# ESP8266_Blind_Board_V2.net
KiCad netlist of a schematic drawn in EasyEDA
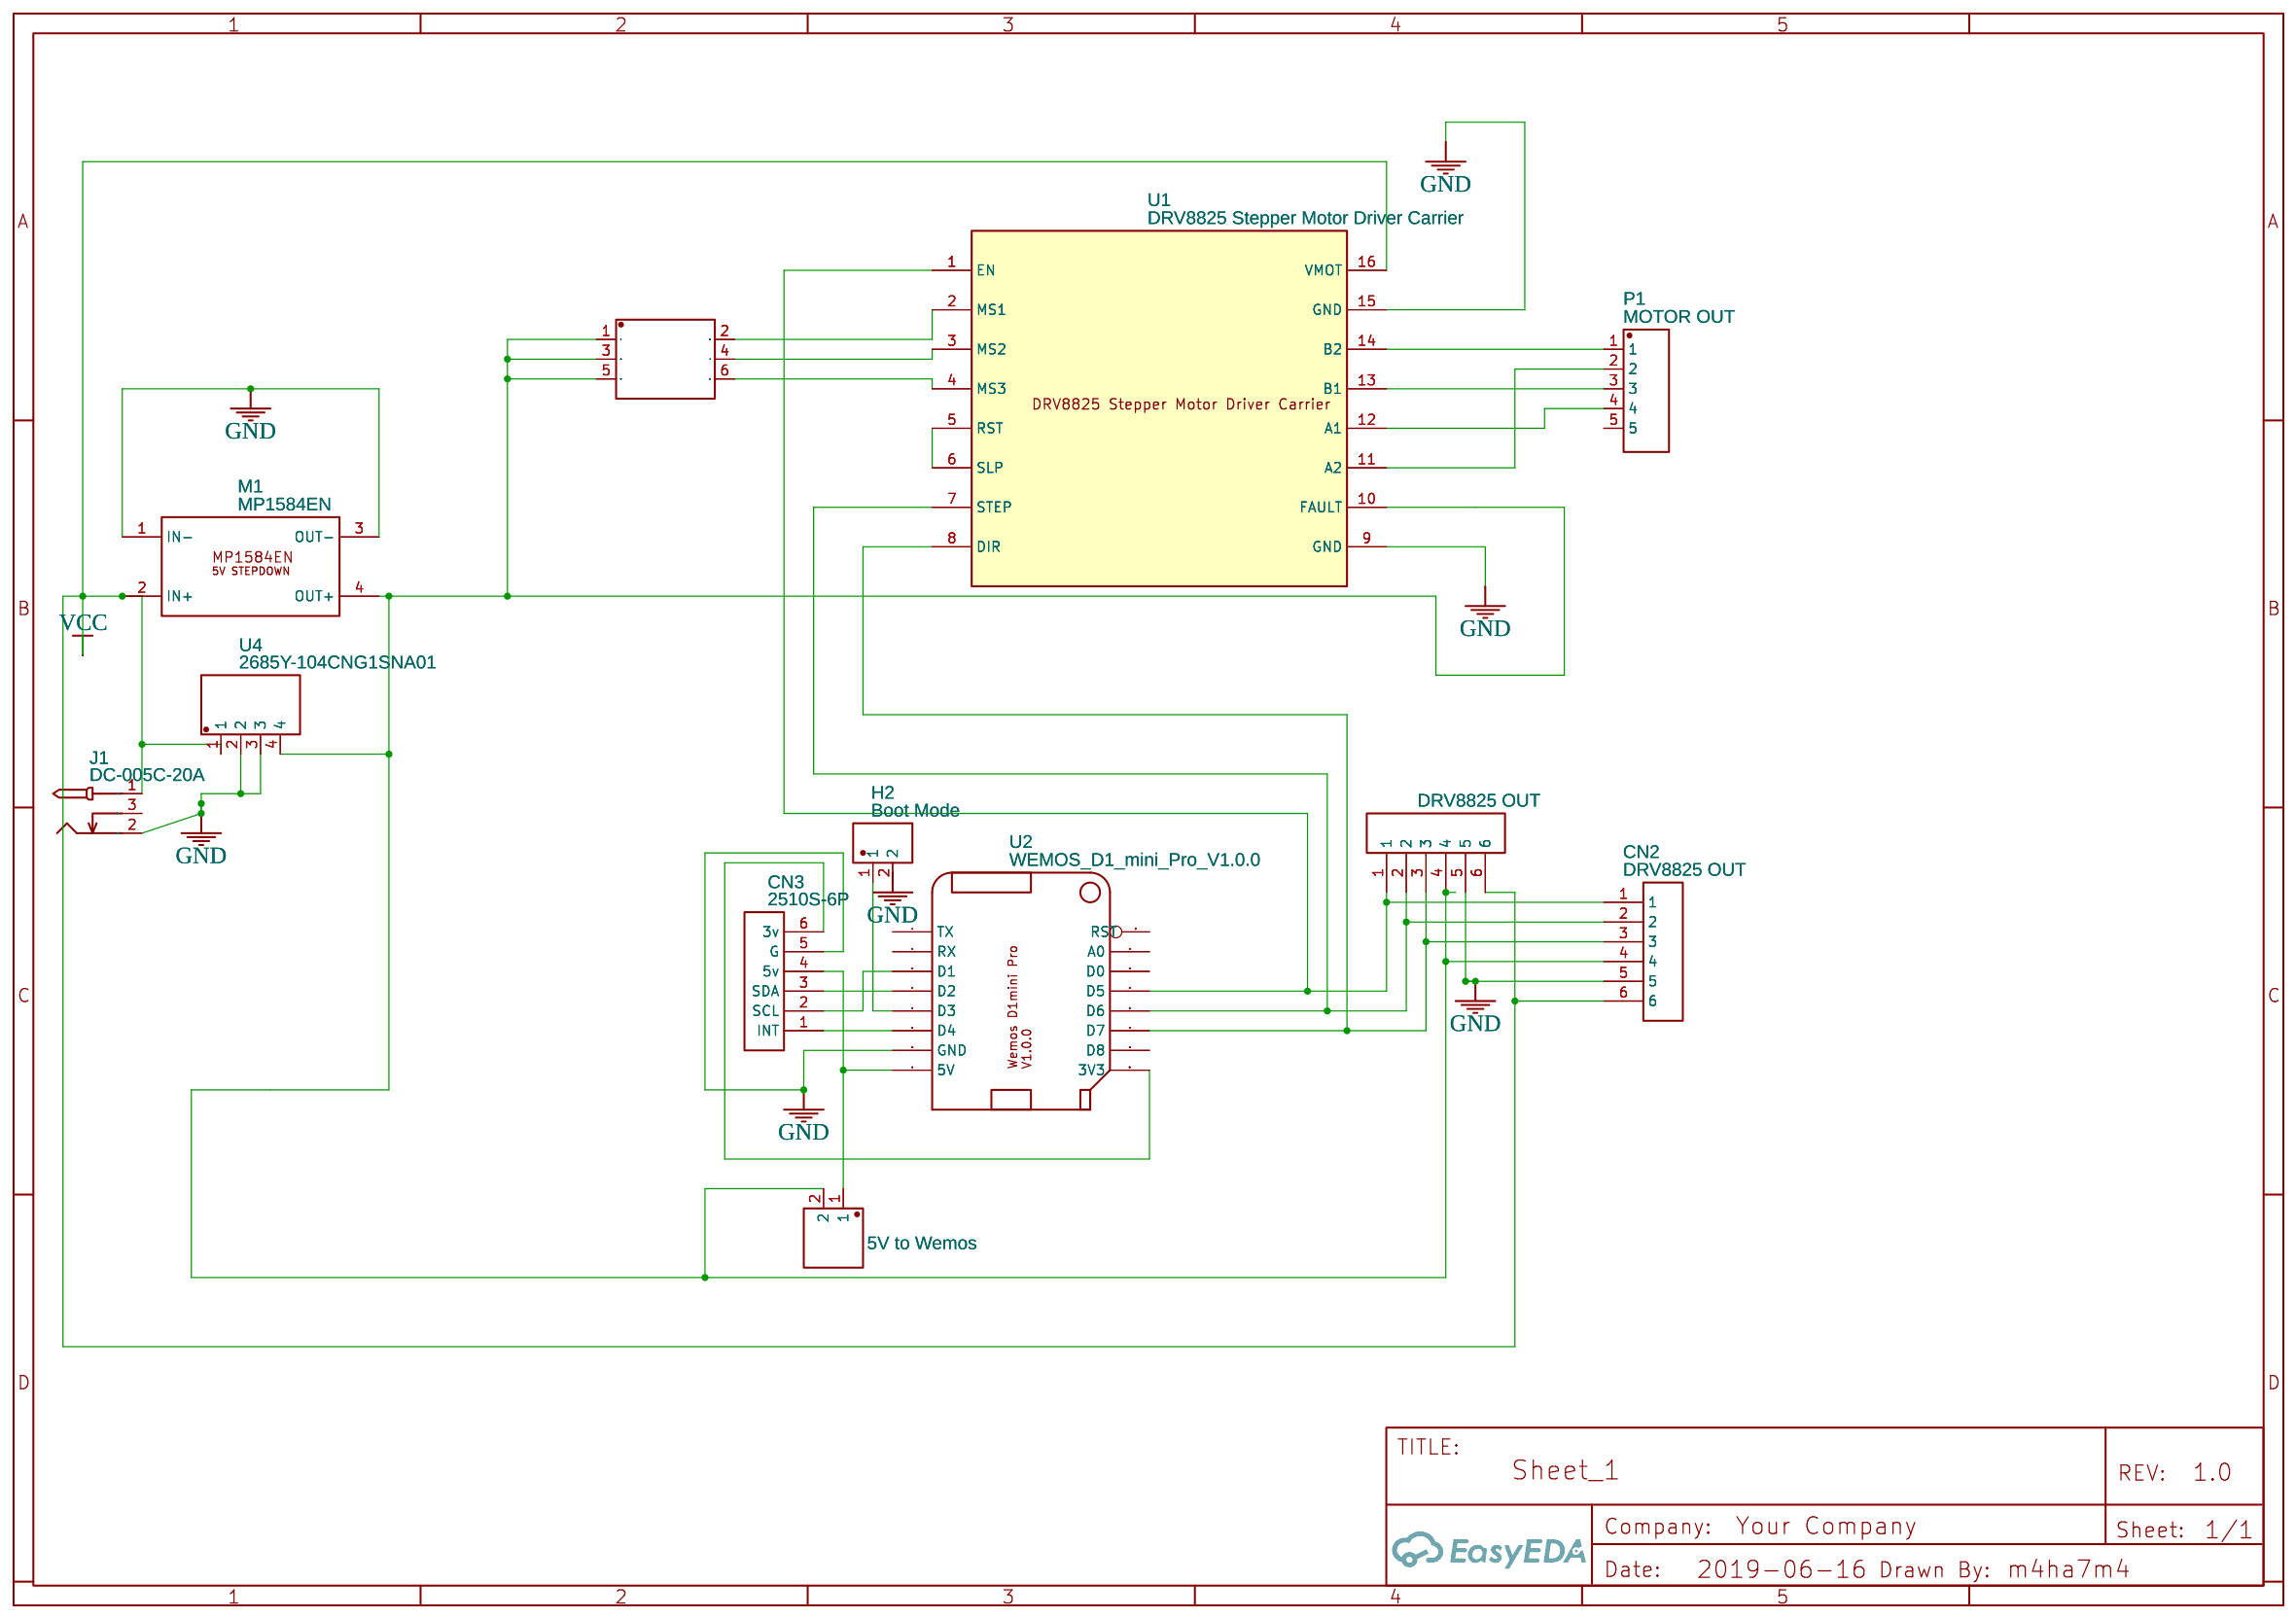
[diagram p0: schematic sheet]

(export (version "E")
  (design (tool "Eeschema 10.0.6"))
  (components
    (comp (ref "CN1")
      (value "DRV8825 OUT")
      (fields (field (name "BOM_Manufacturer Part") "2510S-6P") (field (name "BOM_Supplier Part") "C140771"))
      (libsource (lib "") (part "Unknown_720_425"))
    )
    (comp (ref "CN2")
      (value "DRV8825 OUT")
      (fields (field (name "BOM_Manufacturer Part") "2510S-6P") (field (name "BOM_Supplier Part") "C140771"))
      (libsource (lib "") (part "Unknown_825_475"))
    )
    (comp (ref "CN3")
      (value "2510S-6P")
      (fields (field (name "BOM_Supplier Part") "C140771"))
      (libsource (lib "") (part "Unknown_390_490"))
    )
    (comp (ref "H1")
      (value "5V to Wemos")
      (fields
        (field (name "BOM_Manufacturer Part") "210S-1*2P L=11.6MMGold-plated black")
        (field (name "BOM_Supplier Part") "C124375")
      )
      (libsource (lib "") (part "Unknown_415_615"))
    )
    (comp (ref "H2")
      (value "Boot Mode")
      (fields
        (field (name "BOM_Manufacturer Part") "Z-211-0211-0021-001")
        (field (name "BOM_Supplier Part") "C152154")
      )
      (libsource (lib "") (part "Unknown_440_425"))
    )
    (comp (ref "J1")
      (value "DC-005C-20A")
      (fields (field (name "BOM_Supplier Part") "C84007"))
      (libsource (lib "") (part "Unknown_45_405"))
    )
    (comp (ref "M1") (value "MP1584EN") (libsource (lib "") (part "Unknown_75_305")))
    (comp (ref "P1")
      (value "MOTOR OUT")
      (fields (field (name "BOM_Manufacturer Part") "KF2510-5A") (field (name "BOM_Supplier Part") "C27544"))
      (libsource (lib "") (part "Unknown_820_190"))
    )
    (comp (ref "U1")
      (value "DRV8825 Stepper Motor Driver Carrier")
      (fields (field (name "BOM_Manufacturer Part") "?"))
      (libsource (lib "") (part "Unknown_580_200"))
    )
    (comp (ref "U2")
      (value "WEMOS_D1_mini_Pro_V1.0.0")
      (fields
        (field (name "BOM_Manufacturer Part") "WeMos D1 Mini Pro")
        (field (name "BOM_Supplier Part") "undefined")
      )
      (libsource (lib "") (part "Unknown_505_495"))
    )
    (comp (ref "U4")
      (value "2685Y-104CNG1SNA01")
      (fields (field (name "BOM_Supplier Part") "C350310"))
      (libsource (lib "") (part "Unknown_125_355"))
    )
    (comp (ref "U5")
      (value "MS 1 2 3")
      (fields
        (field (name "BOM_Manufacturer Part") "MTP125-1203S1")
        (field (name "BOM_Supplier Part") "C358692")
      )
      (libsource (lib "") (part "Unknown_330_180"))
    )
  )
  (nets
    (net (code "1") (name "GND") (class "Default")
      (node (ref "CN1") (pin "5") (pinfunction "5_5") (pintype "unspecified"))
      (node (ref "CN2") (pin "5") (pinfunction "5_5") (pintype "unspecified"))
      (node (ref "CN3") (pin "5") (pinfunction "G_5") (pintype "unspecified"))
      (node (ref "H2") (pin "2") (pinfunction "2_2") (pintype "unspecified"))
      (node (ref "J1") (pin "2") (pinfunction "2_2") (pintype "unspecified"))
      (node (ref "M1") (pin "1") (pinfunction "IN-_1") (pintype "unspecified"))
      (node (ref "M1") (pin "3") (pinfunction "OUT-_3") (pintype "unspecified"))
      (node (ref "U1") (pin "15") (pinfunction "GND_15") (pintype "unspecified"))
      (node (ref "U1") (pin "9") (pinfunction "GND_9") (pintype "unspecified"))
      (node (ref "U2") (pin "GND") (pinfunction "GND_GND") (pintype "unspecified"))
      (node (ref "U4") (pin "2") (pinfunction "2_2") (pintype "unspecified"))
      (node (ref "U4") (pin "3") (pinfunction "3_3") (pintype "unspecified"))
    )
    (net (code "2") (name "Net-(CN3-3v)") (class "Default")
      (node (ref "CN3") (pin "6") (pinfunction "3v_6") (pintype "unspecified"))
      (node (ref "U2") (pin "3V3") (pinfunction "3V3_3V3") (pintype "unspecified"))
    )
    (net (code "3") (name "Net-(CN3-5v)") (class "Default")
      (node (ref "CN3") (pin "4") (pinfunction "5v_4") (pintype "unspecified"))
      (node (ref "H1") (pin "1") (pinfunction "1_1") (pintype "unspecified"))
      (node (ref "U2") (pin "5V") (pinfunction "5V_5V") (pintype "unspecified"))
    )
    (net (code "4") (name "Net-(CN3-INT)") (class "Default")
      (node (ref "CN3") (pin "1") (pinfunction "INT_1") (pintype "unspecified"))
      (node (ref "U2") (pin "D4") (pinfunction "D4_D4") (pintype "unspecified"))
    )
    (net (code "5") (name "Net-(CN3-SCL)") (class "Default")
      (node (ref "CN3") (pin "2") (pinfunction "SCL_2") (pintype "unspecified"))
      (node (ref "U2") (pin "D1") (pinfunction "D1_D1") (pintype "unspecified"))
    )
    (net (code "6") (name "Net-(CN3-SDA)") (class "Default")
      (node (ref "CN3") (pin "3") (pinfunction "SDA_3") (pintype "unspecified"))
      (node (ref "U2") (pin "D2") (pinfunction "D2_D2") (pintype "unspecified"))
    )
    (net (code "7") (name "Net-(H2-Pad1)") (class "Default")
      (node (ref "H2") (pin "1") (pinfunction "1_1") (pintype "unspecified"))
      (node (ref "U2") (pin "D3") (pinfunction "D3_D3") (pintype "unspecified"))
    )
    (net (code "8") (name "Net-(M1-OUT+)") (class "Default")
      (node (ref "CN1") (pin "4") (pinfunction "4_4") (pintype "unspecified"))
      (node (ref "CN2") (pin "4") (pinfunction "4_4") (pintype "unspecified"))
      (node (ref "H1") (pin "2") (pinfunction "2_2") (pintype "unspecified"))
      (node (ref "M1") (pin "4") (pinfunction "OUT+_4") (pintype "unspecified"))
      (node (ref "U1") (pin "10") (pinfunction "FAULT_10") (pintype "unspecified"))
      (node (ref "U4") (pin "4") (pinfunction "4_4") (pintype "unspecified"))
      (node (ref "U5") (pin "1") (pinfunction "1_1") (pintype "unspecified"))
      (node (ref "U5") (pin "3") (pinfunction "3_3") (pintype "unspecified"))
      (node (ref "U5") (pin "5") (pinfunction "5_5") (pintype "unspecified"))
    )
    (net (code "9") (name "Net-(U1-A1)") (class "Default")
      (node (ref "P1") (pin "4") (pinfunction "4_4") (pintype "unspecified"))
      (node (ref "U1") (pin "12") (pinfunction "A1_12") (pintype "unspecified"))
    )
    (net (code "10") (name "Net-(U1-A2)") (class "Default")
      (node (ref "P1") (pin "2") (pinfunction "2_2") (pintype "unspecified"))
      (node (ref "U1") (pin "11") (pinfunction "A2_11") (pintype "unspecified"))
    )
    (net (code "11") (name "Net-(U1-B1)") (class "Default")
      (node (ref "P1") (pin "3") (pinfunction "3_3") (pintype "unspecified"))
      (node (ref "U1") (pin "13") (pinfunction "B1_13") (pintype "unspecified"))
    )
    (net (code "12") (name "Net-(U1-B2)") (class "Default")
      (node (ref "P1") (pin "1") (pinfunction "1_1") (pintype "unspecified"))
      (node (ref "U1") (pin "14") (pinfunction "B2_14") (pintype "unspecified"))
    )
    (net (code "13") (name "Net-(U1-DIR)") (class "Default")
      (node (ref "CN1") (pin "3") (pinfunction "3_3") (pintype "unspecified"))
      (node (ref "CN2") (pin "3") (pinfunction "3_3") (pintype "unspecified"))
      (node (ref "U1") (pin "8") (pinfunction "DIR_8") (pintype "unspecified"))
      (node (ref "U2") (pin "D7") (pinfunction "D7_D7") (pintype "unspecified"))
    )
    (net (code "14") (name "Net-(U1-EN)") (class "Default")
      (node (ref "CN1") (pin "1") (pinfunction "1_1") (pintype "unspecified"))
      (node (ref "CN2") (pin "1") (pinfunction "1_1") (pintype "unspecified"))
      (node (ref "U1") (pin "1") (pinfunction "EN_1") (pintype "unspecified"))
      (node (ref "U2") (pin "D5") (pinfunction "D5_D5") (pintype "unspecified"))
    )
    (net (code "15") (name "Net-(U1-MS1)") (class "Default")
      (node (ref "U1") (pin "2") (pinfunction "MS1_2") (pintype "unspecified"))
      (node (ref "U5") (pin "2") (pinfunction "2_2") (pintype "unspecified"))
    )
    (net (code "16") (name "Net-(U1-MS2)") (class "Default")
      (node (ref "U1") (pin "3") (pinfunction "MS2_3") (pintype "unspecified"))
      (node (ref "U5") (pin "4") (pinfunction "4_4") (pintype "unspecified"))
    )
    (net (code "17") (name "Net-(U1-MS3)") (class "Default")
      (node (ref "U1") (pin "4") (pinfunction "MS3_4") (pintype "unspecified"))
      (node (ref "U5") (pin "6") (pinfunction "6_6") (pintype "unspecified"))
    )
    (net (code "18") (name "Net-(U1-RST)") (class "Default")
      (node (ref "U1") (pin "5") (pinfunction "RST_5") (pintype "unspecified"))
      (node (ref "U1") (pin "6") (pinfunction "SLP_6") (pintype "unspecified"))
    )
    (net (code "19") (name "Net-(U1-STEP)") (class "Default")
      (node (ref "CN1") (pin "2") (pinfunction "2_2") (pintype "unspecified"))
      (node (ref "CN2") (pin "2") (pinfunction "2_2") (pintype "unspecified"))
      (node (ref "U1") (pin "7") (pinfunction "STEP_7") (pintype "unspecified"))
      (node (ref "U2") (pin "D6") (pinfunction "D6_D6") (pintype "unspecified"))
    )
    (net (code "20") (name "VCC") (class "Default")
      (node (ref "CN1") (pin "6") (pinfunction "6_6") (pintype "unspecified"))
      (node (ref "CN2") (pin "6") (pinfunction "6_6") (pintype "unspecified"))
      (node (ref "J1") (pin "1") (pinfunction "1_1") (pintype "unspecified"))
      (node (ref "M1") (pin "2") (pinfunction "IN+_2") (pintype "unspecified"))
      (node (ref "U1") (pin "16") (pinfunction "VMOT_16") (pintype "unspecified"))
      (node (ref "U4") (pin "1") (pinfunction "1_1") (pintype "unspecified"))
    )
    (net (code "21") (name "unconnected-(J1-Pad3)") (class "Default")
      (node (ref "J1") (pin "3") (pinfunction "3_3") (pintype "unspecified"))
    )
    (net (code "22") (name "unconnected-(P1-Pad5)") (class "Default")
      (node (ref "P1") (pin "5") (pinfunction "5_5") (pintype "unspecified"))
    )
    (net (code "23") (name "unconnected-(U2-PadA0)") (class "Default")
      (node (ref "U2") (pin "A0") (pinfunction "A0_A0") (pintype "unspecified"))
    )
    (net (code "24") (name "unconnected-(U2-PadD0)") (class "Default")
      (node (ref "U2") (pin "D0") (pinfunction "D0_D0") (pintype "unspecified"))
    )
    (net (code "25") (name "unconnected-(U2-PadD8)") (class "Default")
      (node (ref "U2") (pin "D8") (pinfunction "D8_D8") (pintype "unspecified"))
    )
    (net (code "26") (name "unconnected-(U2-PadRST)") (class "Default")
      (node (ref "U2") (pin "RST") (pinfunction "RST_RST") (pintype "unspecified"))
    )
    (net (code "27") (name "unconnected-(U2-PadRX)") (class "Default")
      (node (ref "U2") (pin "RX") (pinfunction "RX_RX") (pintype "unspecified"))
    )
    (net (code "28") (name "unconnected-(U2-PadTX)") (class "Default")
      (node (ref "U2") (pin "TX") (pinfunction "TX_TX") (pintype "unspecified"))
    )
  )
)
